# POWER.net
KiCad netlist of a schematic drawn in Altium Designer
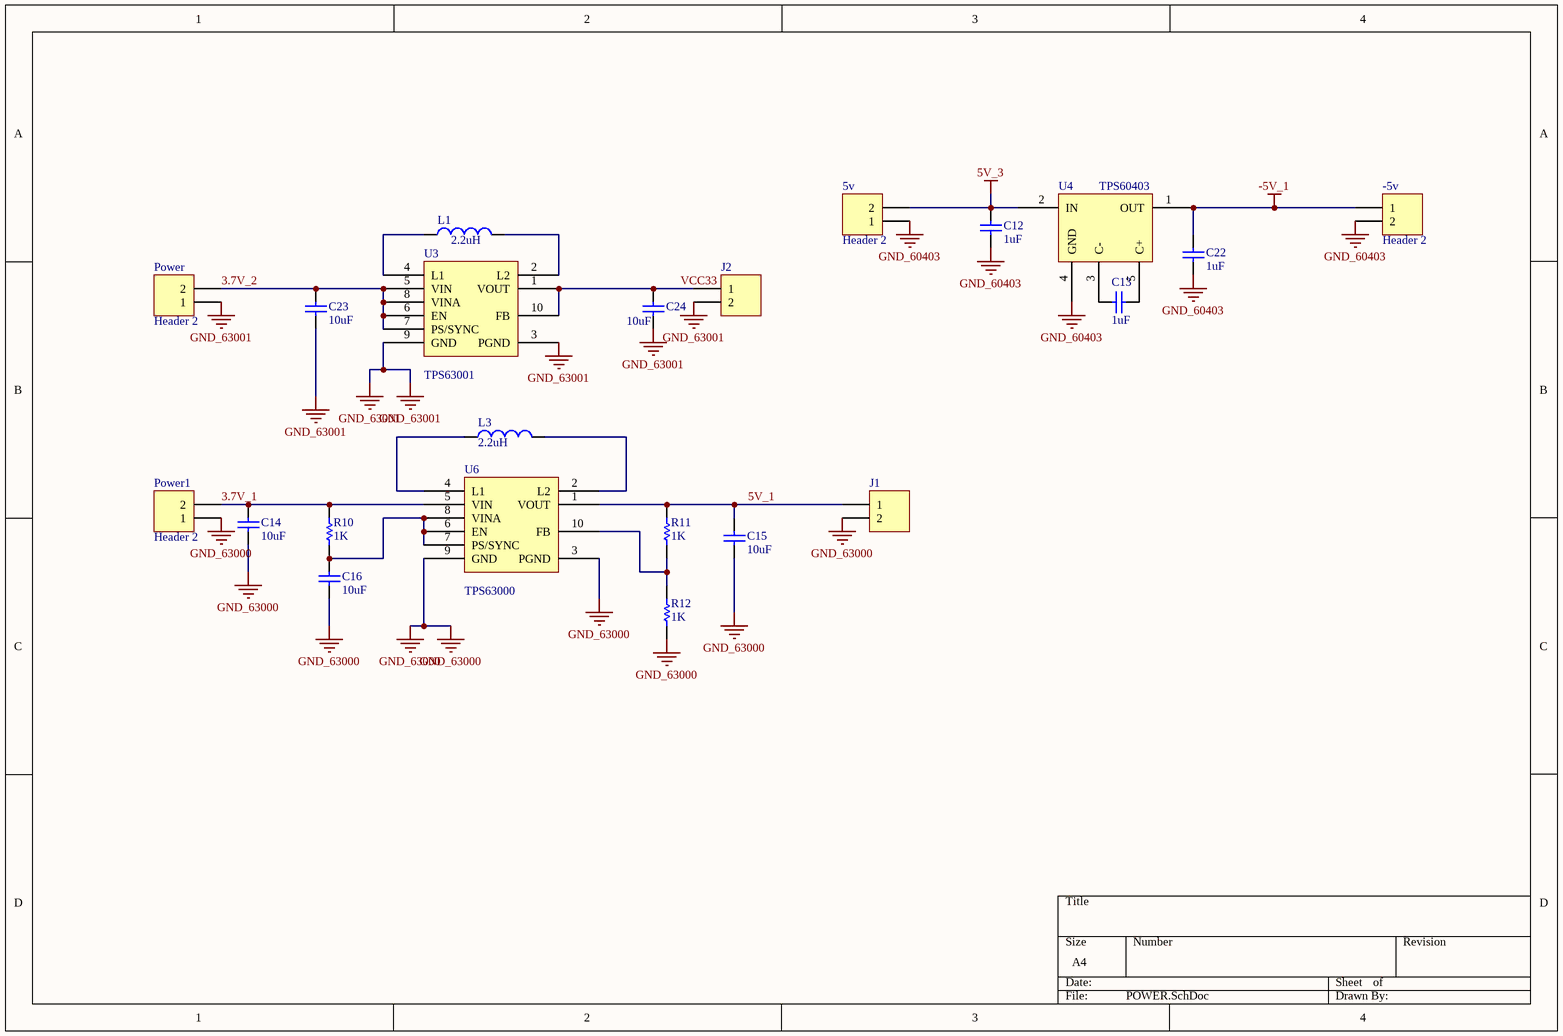
[diagram p0: POWER.SchDoc]

(export (version "E")
  (design (tool "Eeschema 10.0.6"))
  (components
    (comp (ref "-5v")
      (value "Header 2")
      (footprint "HDR1X2")
      (description "Header, 2-Pin")
      (fields (field (name "PUBLISHER") "Altium Limited"))
      (libsource (lib "Miscellaneous Connectors") (part "Header 2"))
    )
    (comp (ref "5v")
      (value "Header 2")
      (footprint "HDR1X2")
      (description "Header, 2-Pin")
      (fields (field (name "PUBLISHER") "Altium Limited"))
      (libsource (lib "") (part "Header 2_1"))
    )
    (comp (ref "C12")
      (value "1uF")
      (footprint "0805封装:PCBComponent_1")
      (description "Capacitor (Semiconductor SIM Model)")
      (fields (field (name "PUBLISHER") "Altium Limited"))
      (libsource (lib "Miscellaneous Devices") (part "Cap Semi"))
    )
    (comp (ref "C13")
      (value "1uF")
      (footprint "0805封装:PCBComponent_1")
      (description "Capacitor (Semiconductor SIM Model)")
      (fields (field (name "PUBLISHER") "Altium Limited"))
      (libsource (lib "Miscellaneous Devices") (part "Cap Semi"))
    )
    (comp (ref "C14")
      (value "10uF")
      (footprint "0805封装:PCBComponent_1")
      (description "Capacitor (Semiconductor SIM Model)")
      (fields (field (name "PUBLISHER") "Altium Limited"))
      (libsource (lib "Miscellaneous Devices") (part "Cap Semi"))
    )
    (comp (ref "C15")
      (value "10uF")
      (footprint "0805封装:PCBComponent_1")
      (description "Capacitor (Semiconductor SIM Model)")
      (fields (field (name "PUBLISHER") "Altium Limited"))
      (libsource (lib "Miscellaneous Devices") (part "Cap Semi"))
    )
    (comp (ref "C16")
      (value "10uF")
      (footprint "0805封装:PCBComponent_1")
      (description "Capacitor (Semiconductor SIM Model)")
      (fields (field (name "PUBLISHER") "Altium Limited"))
      (libsource (lib "Miscellaneous Devices") (part "Cap Semi"))
    )
    (comp (ref "C22")
      (value "1uF")
      (footprint "0805封装:PCBComponent_1")
      (description "Capacitor (Semiconductor SIM Model)")
      (fields (field (name "PUBLISHER") "Altium Limited"))
      (libsource (lib "Miscellaneous Devices") (part "Cap Semi"))
    )
    (comp (ref "C23")
      (value "10uF")
      (footprint "0805封装:PCBComponent_1")
      (description "Capacitor (Semiconductor SIM Model)")
      (fields (field (name "PUBLISHER") "Altium Limited"))
      (libsource (lib "Miscellaneous Devices") (part "Cap Semi"))
    )
    (comp (ref "C24")
      (value "10uF")
      (footprint "0805封装:PCBComponent_1")
      (description "Capacitor (Semiconductor SIM Model)")
      (fields (field (name "PUBLISHER") "Altium Limited"))
      (libsource (lib "Miscellaneous Devices") (part "Cap Semi"))
    )
    (comp (ref "J1")
      (value "~")
      (footprint "HDR1X2")
      (description "Header, 2-Pin")
      (fields (field (name "PUBLISHER") "Altium Limited"))
      (libsource (lib "Miscellaneous Connectors") (part "Header 2"))
    )
    (comp (ref "J2")
      (value "~")
      (footprint "HDR1X2")
      (description "Header, 2-Pin")
      (fields (field (name "PUBLISHER") "Altium Limited"))
      (libsource (lib "Miscellaneous Connectors") (part "Header 2"))
    )
    (comp (ref "L1")
      (value "2.2uH")
      (footprint "INDP7474X40N")
      (description "Inductor")
      (fields (field (name "PUBLISHER") "Altium Limited"))
      (libsource (lib "Miscellaneous Devices") (part "Inductor"))
    )
    (comp (ref "L3")
      (value "2.2uH")
      (footprint "INDP7474X40N")
      (description "Inductor")
      (fields (field (name "PUBLISHER") "Altium Limited"))
      (libsource (lib "Miscellaneous Devices") (part "Inductor"))
    )
    (comp (ref "Power")
      (value "Header 2")
      (footprint "HDR1X2")
      (description "Header, 2-Pin")
      (fields (field (name "PUBLISHER") "Altium Limited"))
      (libsource (lib "") (part "Header 2_1"))
    )
    (comp (ref "Power1")
      (value "Header 2")
      (footprint "HDR1X2")
      (description "Header, 2-Pin")
      (fields (field (name "PUBLISHER") "Altium Limited"))
      (libsource (lib "") (part "Header 2_1"))
    )
    (comp (ref "R10")
      (value "1K")
      (footprint "2012[0805]")
      (description "Semiconductor Resistor")
      (fields (field (name "PUBLISHER") "Altium Limited"))
      (libsource (lib "Miscellaneous Devices") (part "Res Semi"))
    )
    (comp (ref "R11")
      (value "1K")
      (footprint "2012[0805]")
      (description "Semiconductor Resistor")
      (fields (field (name "PUBLISHER") "Altium Limited"))
      (libsource (lib "Miscellaneous Devices") (part "Res Semi"))
    )
    (comp (ref "R12")
      (value "1K")
      (footprint "2012[0805]")
      (description "Semiconductor Resistor")
      (fields (field (name "PUBLISHER") "Altium Limited"))
      (libsource (lib "Miscellaneous Devices") (part "Res Semi"))
    )
    (comp (ref "U3")
      (value "TPS63001")
      (footprint "QFN50P300X300X95-10M")
      (libsource (lib "TPS6300") (part "Component_1"))
    )
    (comp (ref "U4")
      (value "TPS60403")
      (footprint "SOT95P280X110-5N")
      (libsource (lib "TPS60403") (part "Component_1"))
    )
    (comp (ref "U6")
      (value "TPS63000")
      (footprint "QFN50P300X300X95-10M")
      (libsource (lib "TPS6300") (part "Component_1"))
    )
  )
  (nets
    (net (code "1") (name "-5V_1") (class "Default")
      (node (ref "-5v") (pin "1") (pinfunction "1_1") (pintype "passive"))
      (node (ref "C22") (pin "1") (pinfunction "1_1") (pintype "passive"))
      (node (ref "U4") (pin "1") (pinfunction "OUT_1") (pintype "passive"))
    )
    (net (code "2") (name "/3.7V_1") (class "Default")
      (node (ref "C14") (pin "2") (pinfunction "2_2") (pintype "passive"))
      (node (ref "Power1") (pin "2") (pinfunction "2_2") (pintype "passive"))
      (node (ref "R10") (pin "2") (pinfunction "2_2") (pintype "passive"))
      (node (ref "U6") (pin "5") (pinfunction "VIN_5") (pintype "passive"))
    )
    (net (code "3") (name "/3.7V_2") (class "Default")
      (node (ref "C23") (pin "2") (pinfunction "2_2") (pintype "passive"))
      (node (ref "Power") (pin "2") (pinfunction "2_2") (pintype "passive"))
      (node (ref "U3") (pin "5") (pinfunction "VIN_5") (pintype "passive"))
      (node (ref "U3") (pin "6") (pinfunction "EN_6") (pintype "passive"))
      (node (ref "U3") (pin "7") (pinfunction "PS/SYNC_7") (pintype "passive"))
      (node (ref "U3") (pin "8") (pinfunction "VINA_8") (pintype "passive"))
    )
    (net (code "4") (name "/5V_1") (class "Default")
      (node (ref "C15") (pin "2") (pinfunction "2_2") (pintype "passive"))
      (node (ref "J1") (pin "1") (pinfunction "1_1") (pintype "passive"))
      (node (ref "R11") (pin "2") (pinfunction "2_2") (pintype "passive"))
      (node (ref "U6") (pin "1") (pinfunction "VOUT_1") (pintype "passive"))
    )
    (net (code "5") (name "/VCC33") (class "Default")
      (node (ref "C24") (pin "2") (pinfunction "2_2") (pintype "passive"))
      (node (ref "J2") (pin "1") (pinfunction "1_1") (pintype "passive"))
      (node (ref "U3") (pin "1") (pinfunction "VOUT_1") (pintype "passive"))
      (node (ref "U3") (pin "10") (pinfunction "FB_10") (pintype "passive"))
    )
    (net (code "6") (name "5V_3") (class "Default")
      (node (ref "5v") (pin "2") (pinfunction "2_2") (pintype "passive"))
      (node (ref "C12") (pin "1") (pinfunction "1_1") (pintype "passive"))
      (node (ref "U4") (pin "2") (pinfunction "IN_2") (pintype "passive"))
    )
    (net (code "7") (name "GND_60403") (class "Default")
      (node (ref "-5v") (pin "2") (pinfunction "2_2") (pintype "passive"))
      (node (ref "5v") (pin "1") (pinfunction "1_1") (pintype "passive"))
      (node (ref "C12") (pin "2") (pinfunction "2_2") (pintype "passive"))
      (node (ref "C22") (pin "2") (pinfunction "2_2") (pintype "passive"))
      (node (ref "U4") (pin "4") (pinfunction "GND_4") (pintype "passive"))
    )
    (net (code "8") (name "GND_63000") (class "Default")
      (node (ref "C14") (pin "1") (pinfunction "1_1") (pintype "passive"))
      (node (ref "C15") (pin "1") (pinfunction "1_1") (pintype "passive"))
      (node (ref "C16") (pin "1") (pinfunction "1_1") (pintype "passive"))
      (node (ref "J1") (pin "2") (pinfunction "2_2") (pintype "passive"))
      (node (ref "Power1") (pin "1") (pinfunction "1_1") (pintype "passive"))
      (node (ref "R12") (pin "1") (pinfunction "1_1") (pintype "passive"))
      (node (ref "U6") (pin "3") (pinfunction "PGND_3") (pintype "passive"))
      (node (ref "U6") (pin "9") (pinfunction "GND_9") (pintype "passive"))
    )
    (net (code "9") (name "GND_63001") (class "Default")
      (node (ref "C23") (pin "1") (pinfunction "1_1") (pintype "passive"))
      (node (ref "C24") (pin "1") (pinfunction "1_1") (pintype "passive"))
      (node (ref "J2") (pin "2") (pinfunction "2_2") (pintype "passive"))
      (node (ref "Power") (pin "1") (pinfunction "1_1") (pintype "passive"))
      (node (ref "U3") (pin "3") (pinfunction "PGND_3") (pintype "passive"))
      (node (ref "U3") (pin "9") (pinfunction "GND_9") (pintype "passive"))
    )
    (net (code "10") (name "Net-(U3-L1)") (class "Default")
      (node (ref "L1") (pin "1") (pinfunction "1_1") (pintype "passive"))
      (node (ref "U3") (pin "4") (pinfunction "L1_4") (pintype "passive"))
    )
    (net (code "11") (name "Net-(U3-L2)") (class "Default")
      (node (ref "L1") (pin "2") (pinfunction "2_2") (pintype "passive"))
      (node (ref "U3") (pin "2") (pinfunction "L2_2") (pintype "passive"))
    )
    (net (code "12") (name "Net-(U4-C+)") (class "Default")
      (node (ref "C13") (pin "1") (pinfunction "1_1") (pintype "passive"))
      (node (ref "U4") (pin "5") (pinfunction "C+_5") (pintype "passive"))
    )
    (net (code "13") (name "Net-(U4-C-)") (class "Default")
      (node (ref "C13") (pin "2") (pinfunction "2_2") (pintype "passive"))
      (node (ref "U4") (pin "3") (pinfunction "C-_3") (pintype "passive"))
    )
    (net (code "14") (name "Net-(U6-EN)") (class "Default")
      (node (ref "C16") (pin "2") (pinfunction "2_2") (pintype "passive"))
      (node (ref "R10") (pin "1") (pinfunction "1_1") (pintype "passive"))
      (node (ref "U6") (pin "6") (pinfunction "EN_6") (pintype "passive"))
      (node (ref "U6") (pin "7") (pinfunction "PS/SYNC_7") (pintype "passive"))
      (node (ref "U6") (pin "8") (pinfunction "VINA_8") (pintype "passive"))
    )
    (net (code "15") (name "Net-(U6-FB)") (class "Default")
      (node (ref "R11") (pin "1") (pinfunction "1_1") (pintype "passive"))
      (node (ref "R12") (pin "2") (pinfunction "2_2") (pintype "passive"))
      (node (ref "U6") (pin "10") (pinfunction "FB_10") (pintype "passive"))
    )
    (net (code "16") (name "Net-(U6-L1)") (class "Default")
      (node (ref "L3") (pin "1") (pinfunction "1_1") (pintype "passive"))
      (node (ref "U6") (pin "4") (pinfunction "L1_4") (pintype "passive"))
    )
    (net (code "17") (name "Net-(U6-L2)") (class "Default")
      (node (ref "L3") (pin "2") (pinfunction "2_2") (pintype "passive"))
      (node (ref "U6") (pin "2") (pinfunction "L2_2") (pintype "passive"))
    )
  )
)
